# IR_beaconSD.net
KiCad netlist of a schematic drawn in EAGLE
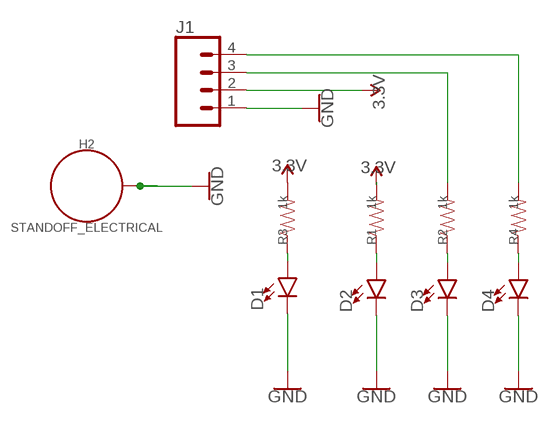
[diagram p0: schematic, sheet 1]

(export (version "E")
  (design (tool "Eeschema 10.0.6"))
  (components
    (comp (ref "D1")
      (value "LED-FKIT-1206")
      (footprint "eagle-import:FKIT-LED-1206")
      (libsource (lib "eagle-import") (part "LED-FKIT-1206"))
    )
    (comp (ref "D2")
      (value "LED-FKIT-1206")
      (footprint "eagle-import:FKIT-LED-1206")
      (libsource (lib "eagle-import") (part "LED-FKIT-1206"))
    )
    (comp (ref "D3")
      (value "LED-FKIT-1206")
      (footprint "eagle-import:FKIT-LED-1206")
      (libsource (lib "eagle-import") (part "LED-FKIT-1206"))
    )
    (comp (ref "D4")
      (value "LED-FKIT-1206")
      (footprint "eagle-import:FKIT-LED-1206")
      (libsource (lib "eagle-import") (part "LED-FKIT-1206"))
    )
    (comp (ref "H2")
      (value "STANDOFF_ELECTRICAL")
      (footprint "eagle-import:STANDOFF-ELECTRICAL")
      (libsource (lib "eagle-import") (part "STANDOFF_ELECTRICAL"))
    )
    (comp (ref "J1")
      (value "CONN_04LONGPADS")
      (footprint "eagle-import:1X04_LONGPADS")
      (libsource (lib "eagle-import") (part "CONN_04LONGPADS"))
    )
    (comp (ref "R1")
      (value "1k")
      (footprint "eagle-import:AXIAL-0.3")
      (libsource (lib "eagle-import") (part "1KOHM-HORIZ-1/4W-5%"))
    )
    (comp (ref "R2")
      (value "1k")
      (footprint "eagle-import:AXIAL-0.3")
      (libsource (lib "eagle-import") (part "1KOHM-HORIZ-1/4W-5%"))
    )
    (comp (ref "R3")
      (value "1k")
      (footprint "eagle-import:AXIAL-0.3")
      (libsource (lib "eagle-import") (part "1KOHM-HORIZ-1/4W-5%"))
    )
    (comp (ref "R4")
      (value "1k")
      (footprint "eagle-import:AXIAL-0.3")
      (libsource (lib "eagle-import") (part "1KOHM-HORIZ-1/4W-5%"))
    )
  )
  (nets
    (net (code "1") (name "3.3V") (class "Default")
      (node (ref "J1") (pin "2") (pinfunction "2_2") (pintype "passive"))
      (node (ref "R1") (pin "P$2") (pinfunction "2_P$2") (pintype "passive"))
      (node (ref "R3") (pin "P$2") (pinfunction "2_P$2") (pintype "passive"))
    )
    (net (code "2") (name "GND") (class "Default")
      (node (ref "D1") (pin "C") (pinfunction "C_C") (pintype "passive"))
      (node (ref "D2") (pin "C") (pinfunction "C_C") (pintype "passive"))
      (node (ref "D3") (pin "C") (pinfunction "C_C") (pintype "passive"))
      (node (ref "D4") (pin "C") (pinfunction "C_C") (pintype "passive"))
      (node (ref "H2") (pin "P1") (pinfunction "P$1_P1") (pintype "bidirectional"))
      (node (ref "J1") (pin "1") (pinfunction "1_1") (pintype "passive"))
    )
    (net (code "3") (name "Net-(R1-1)") (class "Default")
      (node (ref "D2") (pin "A") (pinfunction "A_A") (pintype "passive"))
      (node (ref "R1") (pin "P$1") (pinfunction "1_P$1") (pintype "passive"))
    )
    (net (code "4") (name "Net-(R2-1)") (class "Default")
      (node (ref "D3") (pin "A") (pinfunction "A_A") (pintype "passive"))
      (node (ref "R2") (pin "P$1") (pinfunction "1_P$1") (pintype "passive"))
    )
    (net (code "5") (name "Net-(R2-2)") (class "Default")
      (node (ref "J1") (pin "3") (pinfunction "3_3") (pintype "passive"))
      (node (ref "R2") (pin "P$2") (pinfunction "2_P$2") (pintype "passive"))
    )
    (net (code "6") (name "Net-(R3-1)") (class "Default")
      (node (ref "D1") (pin "A") (pinfunction "A_A") (pintype "passive"))
      (node (ref "R3") (pin "P$1") (pinfunction "1_P$1") (pintype "passive"))
    )
    (net (code "7") (name "Net-(R4-1)") (class "Default")
      (node (ref "D4") (pin "A") (pinfunction "A_A") (pintype "passive"))
      (node (ref "R4") (pin "P$1") (pinfunction "1_P$1") (pintype "passive"))
    )
    (net (code "8") (name "Net-(R4-2)") (class "Default")
      (node (ref "J1") (pin "4") (pinfunction "4_4") (pintype "passive"))
      (node (ref "R4") (pin "P$2") (pinfunction "2_P$2") (pintype "passive"))
    )
  )
)
